# M18_lcq_20140714.net
KiCad netlist of a schematic drawn in Altium Designer
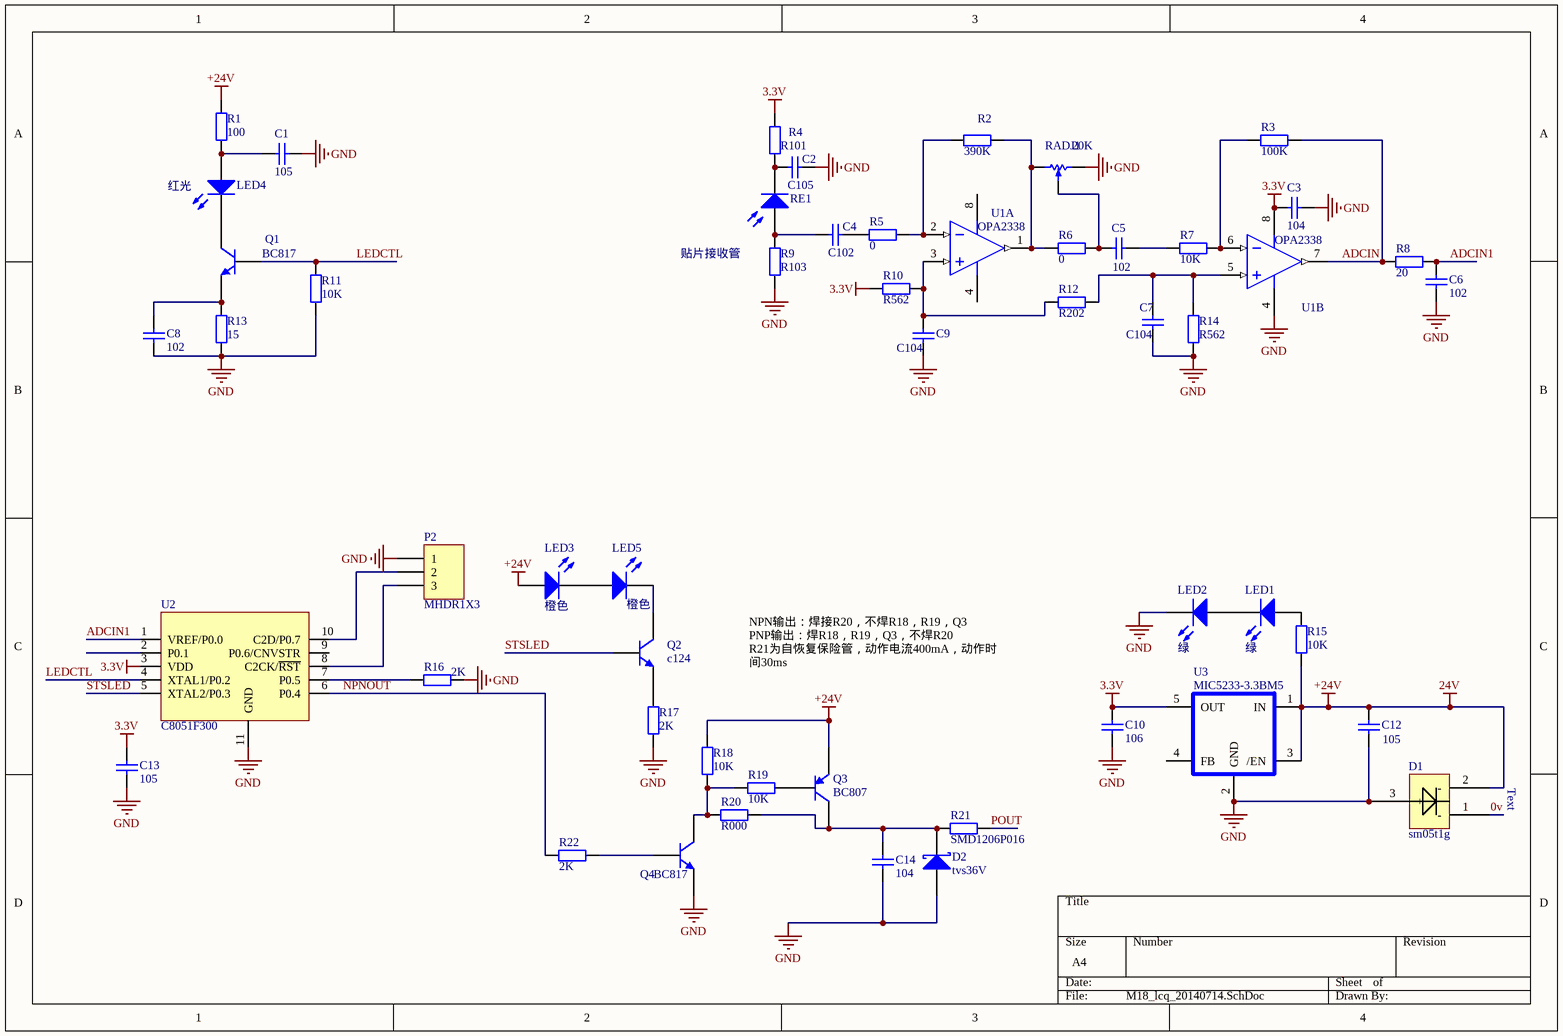
[diagram p0: M18_lcq_20140714.SchDoc]

(export (version "E")
  (design (tool "Eeschema 10.0.6"))
  (components
    (comp (ref "C1")
      (value "105")
      (footprint "C0805")
      (description "Capacitor")
      (fields (field (name "PUBLISHER") "Altium Limited"))
      (libsource (lib "TMJD1.0") (part "Cap"))
    )
    (comp (ref "C2")
      (value "C105")
      (footprint "C0603")
      (description "Capacitor")
      (fields (field (name "Comment") "C104") (field (name "PUBLISHER") "Altium Limited"))
      (libsource (lib "TMJD1.0") (part "Cap"))
    )
    (comp (ref "C3")
      (value "104")
      (footprint "C0805")
      (description "Capacitor")
      (fields (field (name "Comment") "C106") (field (name "PUBLISHER") "Altium Limited"))
      (libsource (lib "TMJD1.0") (part "Cap"))
    )
    (comp (ref "C4")
      (value "C102")
      (footprint "C0603")
      (description "Capacitor")
      (fields (field (name "Comment") "C104") (field (name "PUBLISHER") "Altium Limited"))
      (libsource (lib "TMJD1.0") (part "Cap"))
    )
    (comp (ref "C5")
      (value "102")
      (footprint "C0603")
      (description "Capacitor")
      (fields (field (name "Comment") "C104") (field (name "PUBLISHER") "Altium Limited"))
      (libsource (lib "TMJD1.0") (part "Cap"))
    )
    (comp (ref "C6")
      (value "102")
      (footprint "C0603")
      (description "Capacitor")
      (fields (field (name "Comment") "C104") (field (name "PUBLISHER") "Altium Limited"))
      (libsource (lib "TMJD1.0") (part "Cap"))
    )
    (comp (ref "C7")
      (value "C104")
      (footprint "C0603")
      (description "Capacitor")
      (fields (field (name "PUBLISHER") "Altium Limited"))
      (libsource (lib "TMJD1.0") (part "Cap"))
    )
    (comp (ref "C8")
      (value "102")
      (footprint "C0603")
      (description "Capacitor")
      (fields (field (name "Comment") "C104") (field (name "PUBLISHER") "Altium Limited"))
      (libsource (lib "TMJD1.0") (part "Cap"))
    )
    (comp (ref "C9")
      (value "C104")
      (footprint "C0603")
      (description "Capacitor")
      (fields (field (name "PUBLISHER") "Altium Limited"))
      (libsource (lib "TMJD1.0") (part "Cap"))
    )
    (comp (ref "C10")
      (value "106")
      (footprint "C0805")
      (description "Capacitor")
      (fields (field (name "Comment") "C106") (field (name "PUBLISHER") "Altium Limited"))
      (libsource (lib "TMJD1.0") (part "Cap"))
    )
    (comp (ref "C12")
      (value "105")
      (footprint "C0805")
      (description "Capacitor")
      (fields (field (name "PUBLISHER") "Altium Limited"))
      (libsource (lib "TMJD1.0") (part "Cap"))
    )
    (comp (ref "C13")
      (value "105")
      (footprint "C0805")
      (description "Capacitor")
      (fields (field (name "Comment") "C106") (field (name "PUBLISHER") "Altium Limited"))
      (libsource (lib "TMJD1.0") (part "Cap"))
    )
    (comp (ref "C14")
      (value "104")
      (footprint "C0603")
      (description "Capacitor")
      (fields (field (name "Comment") "C104") (field (name "PUBLISHER") "Altium Limited"))
      (libsource (lib "TMJD1.0") (part "Cap"))
    )
    (comp (ref "D1") (value "sm05t1g") (footprint "SOT23A") (libsource (lib "sm05t1g") (part "sm05t1g")))
    (comp (ref "D2")
      (value "tvs36V")
      (footprint "QQ2440V3封装库:3216A")
      (description "Schottky Diode")
      (fields (field (name "PUBLISHER") "Altium Limited"))
      (libsource (lib "*") (part "D Schottky"))
    )
    (comp (ref "LED1")
      (value "绿")
      (footprint "d0603")
      (description "Typical INFRARED GaAs LED")
      (fields (field (name "PUBLISHER") "Altium Limited"))
      (libsource (lib "Miscellaneous Devices") (part "LED0"))
    )
    (comp (ref "LED2")
      (value "绿")
      (footprint "d0603")
      (description "Typical INFRARED GaAs LED")
      (fields (field (name "PUBLISHER") "Altium Limited"))
      (libsource (lib "Miscellaneous Devices") (part "LED0"))
    )
    (comp (ref "LED3")
      (value "橙色")
      (footprint "d0603")
      (description "Typical INFRARED GaAs LED")
      (fields (field (name "PUBLISHER") "Altium Limited"))
      (libsource (lib "Miscellaneous Devices") (part "LED0"))
    )
    (comp (ref "LED4")
      (value "红光")
      (footprint "LED-1210")
      (description "Typical INFRARED GaAs LED")
      (fields (field (name "PUBLISHER") "Altium Limited"))
      (libsource (lib "Miscellaneous Devices") (part "LED0"))
    )
    (comp (ref "LED5")
      (value "橙色")
      (footprint "d0603")
      (description "Typical INFRARED GaAs LED")
      (fields (field (name "PUBLISHER") "Altium Limited"))
      (libsource (lib "Miscellaneous Devices") (part "LED0"))
    )
    (comp (ref "P2")
      (value "MHDR1X3")
      (footprint "MHDR1X3")
      (description "Header, 3-Pin")
      (fields (field (name "PUBLISHER") "Altium Limited"))
      (libsource (lib "Miscellaneous Connectors") (part "MHDR1X3"))
    )
    (comp (ref "Q1")
      (value "BC817")
      (footprint "SOT23A")
      (description "NPN Switching Transistor")
      (fields (field (name "PUBLISHER") "Altium Limited"))
      (libsource (lib "*") (part "MMBT3904"))
    )
    (comp (ref "Q2")
      (value "c124")
      (footprint "SOT23A")
      (description "NPN Switching Transistor")
      (fields (field (name "PUBLISHER") "Altium Limited"))
      (libsource (lib "*") (part "MMBT3904"))
    )
    (comp (ref "Q3")
      (value "BC807")
      (footprint "SOT23A")
      (description "PNP Switching Transistor")
      (fields (field (name "PUBLISHER") "Altium Limited"))
      (libsource (lib "Philips Discrete BJT - Low Power") (part "MMBT3906"))
    )
    (comp (ref "Q4")
      (value "BC817")
      (footprint "SOT23A")
      (description "NPN Switching Transistor")
      (fields (field (name "PUBLISHER") "Altium Limited"))
      (libsource (lib "*") (part "MMBT3904"))
    )
    (comp (ref "R1")
      (value "100")
      (footprint "R0603")
      (description "Resistor")
      (fields (field (name "PUBLISHER") "Altium Limited"))
      (libsource (lib "") (part "Res2_3"))
    )
    (comp (ref "R2")
      (value "390K")
      (footprint "R0603-A")
      (description "Resistor")
      (fields (field (name "PUBLISHER") "Altium Limited"))
      (libsource (lib "") (part "Res2_2"))
    )
    (comp (ref "R3")
      (value "100K")
      (footprint "R0603-A")
      (description "Resistor")
      (fields (field (name "PUBLISHER") "Altium Limited"))
      (libsource (lib "") (part "Res2_2"))
    )
    (comp (ref "R4")
      (value "R101")
      (footprint "R0603-A")
      (description "Resistor")
      (fields (field (name "PUBLISHER") "Altium Limited"))
      (libsource (lib "") (part "Res2_3"))
    )
    (comp (ref "R5")
      (value "0")
      (footprint "R0603-A")
      (description "Resistor")
      (fields (field (name "PUBLISHER") "Altium Limited"))
      (libsource (lib "") (part "Res2_2"))
    )
    (comp (ref "R6")
      (value "0")
      (footprint "R0603-A")
      (description "Resistor")
      (fields (field (name "PUBLISHER") "Altium Limited"))
      (libsource (lib "") (part "Res2_2"))
    )
    (comp (ref "R7")
      (value "10K")
      (footprint "R0603-A")
      (description "Resistor")
      (fields (field (name "PUBLISHER") "Altium Limited"))
      (libsource (lib "") (part "Res2_1"))
    )
    (comp (ref "R8")
      (value "20")
      (footprint "R0603-A")
      (description "Resistor")
      (fields (field (name "PUBLISHER") "Altium Limited"))
      (libsource (lib "") (part "Res2_2"))
    )
    (comp (ref "R9")
      (value "R103")
      (footprint "R0603-A")
      (description "Resistor")
      (fields (field (name "PUBLISHER") "Altium Limited"))
      (libsource (lib "") (part "Res2_3"))
    )
    (comp (ref "R10")
      (value "R562")
      (footprint "R0603-A")
      (description "Resistor")
      (fields (field (name "PUBLISHER") "Altium Limited"))
      (libsource (lib "") (part "Res2_1"))
    )
    (comp (ref "R11")
      (value "10K")
      (footprint "R0603-A")
      (description "Resistor")
      (fields (field (name "PUBLISHER") "Altium Limited"))
      (libsource (lib "Miscellaneous Devices") (part "Res2"))
    )
    (comp (ref "R12")
      (value "R202")
      (footprint "R0603-A")
      (description "Resistor")
      (fields (field (name "PUBLISHER") "Altium Limited"))
      (libsource (lib "") (part "Res2_2"))
    )
    (comp (ref "R13")
      (value "15")
      (footprint "R0603-A")
      (description "Resistor")
      (fields (field (name "PUBLISHER") "Altium Limited"))
      (libsource (lib "Miscellaneous Devices") (part "Res2"))
    )
    (comp (ref "R14")
      (value "R562")
      (footprint "R0603-A")
      (description "Resistor")
      (fields (field (name "PUBLISHER") "Altium Limited"))
      (libsource (lib "") (part "Res2_3"))
    )
    (comp (ref "R15")
      (value "10K")
      (footprint "R0603-A")
      (description "Resistor")
      (fields (field (name "PUBLISHER") "Altium Limited"))
      (libsource (lib "Miscellaneous Devices") (part "Res2"))
    )
    (comp (ref "R16")
      (value "2K")
      (footprint "R0603-A")
      (description "Resistor")
      (fields (field (name "PUBLISHER") "Altium Limited"))
      (libsource (lib "") (part "Res2_2"))
    )
    (comp (ref "R17")
      (value "2K")
      (footprint "R0603-A")
      (description "Resistor")
      (fields (field (name "PUBLISHER") "Altium Limited"))
      (libsource (lib "Miscellaneous Devices") (part "Res2"))
    )
    (comp (ref "R18")
      (value "10K")
      (footprint "R0603-A")
      (description "Resistor")
      (fields (field (name "PUBLISHER") "Altium Limited"))
      (libsource (lib "") (part "Res2_3"))
    )
    (comp (ref "R19")
      (value "10K")
      (footprint "R0603-A")
      (description "Resistor")
      (fields (field (name "PUBLISHER") "Altium Limited"))
      (libsource (lib "") (part "Res2_2"))
    )
    (comp (ref "R20")
      (value "R000")
      (footprint "R0603-A")
      (description "Resistor")
      (fields (field (name "PUBLISHER") "Altium Limited"))
      (libsource (lib "") (part "Res2_2"))
    )
    (comp (ref "R21")
      (value "SMD1206P016")
      (footprint "QQ2440V3封装库:3216A")
      (description "Resistor")
      (fields (field (name "PUBLISHER") "Altium Limited"))
      (libsource (lib "") (part "Res2_2"))
    )
    (comp (ref "R22")
      (value "2K")
      (footprint "R0603-A")
      (description "Resistor")
      (fields (field (name "PUBLISHER") "Altium Limited"))
      (libsource (lib "") (part "Res2_1"))
    )
    (comp (ref "RADJ1")
      (value "20K")
      (footprint "POT4MM-2")
      (description "Square Trimming Potentiometer")
      (fields (field (name "PUBLISHER") "Altium Limited"))
      (libsource (lib "Miscellaneous Devices") (part "RPot SM"))
    )
    (comp (ref "RE1")
      (value "贴片接收管")
      (footprint "LED-1210")
      (description "Photosensitive Diode")
      (fields (field (name "PUBLISHER") "Altium Limited"))
      (libsource (lib "Miscellaneous Devices") (part "Photo Sen"))
    )
    (comp (ref "U1")
      (value "OPA2338")
      (footprint "SOT23-8")
      (description "Dual Low Noise, Audio Amplifier")
      (fields (field (name "PUBLISHER") "Altium Limited"))
      (libsource (lib "Motorola Amplifier Audio Amplifier") (part "LM833D"))
    )
    (comp (ref "U2")
      (value "C8051F300")
      (footprint "C8051F330:IC*")
      (libsource (lib "集成块") (part "PIC16C505"))
    )
    (comp (ref "U3")
      (value "MIC5233-3.3BM5")
      (footprint "SOT-457")
      (libsource (lib "电源管理") (part "TPS77001"))
    )
  )
  (nets
    (net (code "1") (name "+24V") (class "Default")
      (node (ref "C12") (pin "1") (pinfunction "1_1") (pintype "passive"))
      (node (ref "D1") (pin "2") (pinfunction "-_2") (pintype "passive"))
      (node (ref "LED3") (pin "1") (pinfunction "A_1") (pintype "passive"))
      (node (ref "Q3") (pin "2") (pinfunction "E_2") (pintype "passive"))
      (node (ref "R1") (pin "1") (pinfunction "1_1") (pintype "passive"))
      (node (ref "R15") (pin "1") (pinfunction "1_1") (pintype "passive"))
      (node (ref "R18") (pin "1") (pinfunction "1_1") (pintype "passive"))
      (node (ref "U3") (pin "1") (pinfunction "IN_1") (pintype "passive"))
      (node (ref "U3") (pin "3") (pinfunction "/EN_3") (pintype "passive"))
    )
    (net (code "2") (name "/0v") (class "Default")
      (node (ref "D1") (pin "1") (pinfunction "-_1") (pintype "passive"))
    )
    (net (code "3") (name "/ADCIN") (class "Default")
      (node (ref "R3") (pin "2") (pinfunction "2_2") (pintype "passive"))
      (node (ref "R8") (pin "1") (pinfunction "1_1") (pintype "passive"))
      (node (ref "U1") (pin "7") (pinfunction "OUT_7") (pintype "output"))
    )
    (net (code "4") (name "/ADCIN1") (class "Default")
      (node (ref "C6") (pin "2") (pinfunction "2_2") (pintype "passive"))
      (node (ref "R8") (pin "2") (pinfunction "2_2") (pintype "passive"))
      (node (ref "U2") (pin "1") (pinfunction "VREF/P0.0_1") (pintype "passive"))
    )
    (net (code "5") (name "/LEDCTL") (class "Default")
      (node (ref "Q1") (pin "1") (pinfunction "B_1") (pintype "passive"))
      (node (ref "R11") (pin "2") (pinfunction "2_2") (pintype "passive"))
      (node (ref "U2") (pin "4") (pinfunction "XTAL1/P0.2_4") (pintype "passive"))
    )
    (net (code "6") (name "/NPNOUT") (class "Default")
      (node (ref "R22") (pin "2") (pinfunction "2_2") (pintype "passive"))
      (node (ref "U2") (pin "6") (pinfunction "P0.4_6") (pintype "passive"))
    )
    (net (code "7") (name "/POUT") (class "Default")
      (node (ref "R21") (pin "2") (pinfunction "2_2") (pintype "passive"))
    )
    (net (code "8") (name "/STSLED") (class "Default")
      (node (ref "Q2") (pin "1") (pinfunction "B_1") (pintype "passive"))
      (node (ref "U2") (pin "5") (pinfunction "XTAL2/P0.3_5") (pintype "passive"))
    )
    (net (code "9") (name "3.3V") (class "Default")
      (node (ref "C10") (pin "1") (pinfunction "1_1") (pintype "passive"))
      (node (ref "C13") (pin "1") (pinfunction "1_1") (pintype "passive"))
      (node (ref "C3") (pin "1") (pinfunction "1_1") (pintype "passive"))
      (node (ref "R10") (pin "2") (pinfunction "2_2") (pintype "passive"))
      (node (ref "R4") (pin "1") (pinfunction "1_1") (pintype "passive"))
      (node (ref "U1") (pin "8") (pinfunction "VCC_8") (pintype "power_in"))
      (node (ref "U2") (pin "3") (pinfunction "VDD_3") (pintype "passive"))
      (node (ref "U3") (pin "5") (pinfunction "OUT_5") (pintype "passive"))
    )
    (net (code "10") (name "GND") (class "Default")
      (node (ref "C1") (pin "2") (pinfunction "2_2") (pintype "passive"))
      (node (ref "C10") (pin "2") (pinfunction "2_2") (pintype "passive"))
      (node (ref "C12") (pin "2") (pinfunction "2_2") (pintype "passive"))
      (node (ref "C13") (pin "2") (pinfunction "2_2") (pintype "passive"))
      (node (ref "C14") (pin "2") (pinfunction "2_2") (pintype "passive"))
      (node (ref "C2") (pin "2") (pinfunction "2_2") (pintype "passive"))
      (node (ref "C3") (pin "2") (pinfunction "2_2") (pintype "passive"))
      (node (ref "C6") (pin "1") (pinfunction "1_1") (pintype "passive"))
      (node (ref "C7") (pin "2") (pinfunction "2_2") (pintype "passive"))
      (node (ref "C8") (pin "2") (pinfunction "2_2") (pintype "passive"))
      (node (ref "C9") (pin "2") (pinfunction "2_2") (pintype "passive"))
      (node (ref "D1") (pin "3") (pinfunction "+_3") (pintype "passive"))
      (node (ref "D2") (pin "1") (pinfunction "A_1") (pintype "passive"))
      (node (ref "LED2") (pin "2") (pinfunction "K_2") (pintype "passive"))
      (node (ref "P2") (pin "1") (pinfunction "1_1") (pintype "passive"))
      (node (ref "Q4") (pin "2") (pinfunction "E_2") (pintype "passive"))
      (node (ref "R11") (pin "1") (pinfunction "1_1") (pintype "passive"))
      (node (ref "R13") (pin "1") (pinfunction "1_1") (pintype "passive"))
      (node (ref "R14") (pin "2") (pinfunction "2_2") (pintype "passive"))
      (node (ref "R16") (pin "2") (pinfunction "2_2") (pintype "passive"))
      (node (ref "R17") (pin "1") (pinfunction "1_1") (pintype "passive"))
      (node (ref "R9") (pin "2") (pinfunction "2_2") (pintype "passive"))
      (node (ref "RADJ1") (pin "CW") (pinfunction "+_CW") (pintype "passive"))
      (node (ref "U1") (pin "4") (pinfunction "VEE_4") (pintype "power_in"))
      (node (ref "U2") (pin "11") (pinfunction "GND_11") (pintype "passive"))
      (node (ref "U3") (pin "2") (pinfunction "GND_2") (pintype "passive"))
    )
    (net (code "11") (name "Net-(C4-Pad2)") (class "Default")
      (node (ref "C4") (pin "2") (pinfunction "2_2") (pintype "passive"))
      (node (ref "R5") (pin "1") (pinfunction "1_1") (pintype "passive"))
    )
    (net (code "12") (name "Net-(C5-Pad1)") (class "Default")
      (node (ref "C5") (pin "1") (pinfunction "1_1") (pintype "passive"))
      (node (ref "R6") (pin "2") (pinfunction "2_2") (pintype "passive"))
      (node (ref "RADJ1") (pin "W") (pinfunction "W_W") (pintype "passive"))
    )
    (net (code "13") (name "Net-(C5-Pad2)") (class "Default")
      (node (ref "C5") (pin "2") (pinfunction "2_2") (pintype "passive"))
      (node (ref "R7") (pin "2") (pinfunction "2_2") (pintype "passive"))
    )
    (net (code "14") (name "Net-(D2-K)") (class "Default")
      (node (ref "C14") (pin "1") (pinfunction "1_1") (pintype "passive"))
      (node (ref "D2") (pin "2") (pinfunction "K_2") (pintype "passive"))
      (node (ref "Q3") (pin "3") (pinfunction "C_3") (pintype "passive"))
      (node (ref "R20") (pin "2") (pinfunction "2_2") (pintype "passive"))
      (node (ref "R21") (pin "1") (pinfunction "1_1") (pintype "passive"))
    )
    (net (code "15") (name "Net-(LED1-A)") (class "Default")
      (node (ref "LED1") (pin "1") (pinfunction "A_1") (pintype "passive"))
      (node (ref "R15") (pin "2") (pinfunction "2_2") (pintype "passive"))
    )
    (net (code "16") (name "Net-(LED1-K)") (class "Default")
      (node (ref "LED1") (pin "2") (pinfunction "K_2") (pintype "passive"))
      (node (ref "LED2") (pin "1") (pinfunction "A_1") (pintype "passive"))
    )
    (net (code "17") (name "Net-(LED3-K)") (class "Default")
      (node (ref "LED3") (pin "2") (pinfunction "K_2") (pintype "passive"))
      (node (ref "LED5") (pin "1") (pinfunction "A_1") (pintype "passive"))
    )
    (net (code "18") (name "Net-(LED4-A)") (class "Default")
      (node (ref "C1") (pin "1") (pinfunction "1_1") (pintype "passive"))
      (node (ref "LED4") (pin "1") (pinfunction "A_1") (pintype "passive"))
      (node (ref "R1") (pin "2") (pinfunction "2_2") (pintype "passive"))
    )
    (net (code "19") (name "Net-(LED4-K)") (class "Default")
      (node (ref "LED4") (pin "2") (pinfunction "K_2") (pintype "passive"))
      (node (ref "Q1") (pin "3") (pinfunction "C_3") (pintype "passive"))
    )
    (net (code "20") (name "Net-(LED5-K)") (class "Default")
      (node (ref "LED5") (pin "2") (pinfunction "K_2") (pintype "passive"))
      (node (ref "Q2") (pin "3") (pinfunction "C_3") (pintype "passive"))
    )
    (net (code "21") (name "Net-(Q1-E)") (class "Default")
      (node (ref "C8") (pin "1") (pinfunction "1_1") (pintype "passive"))
      (node (ref "Q1") (pin "2") (pinfunction "E_2") (pintype "passive"))
      (node (ref "R13") (pin "2") (pinfunction "2_2") (pintype "passive"))
    )
    (net (code "22") (name "Net-(Q2-E)") (class "Default")
      (node (ref "Q2") (pin "2") (pinfunction "E_2") (pintype "passive"))
      (node (ref "R17") (pin "2") (pinfunction "2_2") (pintype "passive"))
    )
    (net (code "23") (name "Net-(Q3-B)") (class "Default")
      (node (ref "Q3") (pin "1") (pinfunction "B_1") (pintype "passive"))
      (node (ref "R19") (pin "2") (pinfunction "2_2") (pintype "passive"))
    )
    (net (code "24") (name "Net-(Q4-B)") (class "Default")
      (node (ref "Q4") (pin "1") (pinfunction "B_1") (pintype "passive"))
      (node (ref "R22") (pin "1") (pinfunction "1_1") (pintype "passive"))
    )
    (net (code "25") (name "Net-(Q4-C)") (class "Default")
      (node (ref "Q4") (pin "3") (pinfunction "C_3") (pintype "passive"))
      (node (ref "R18") (pin "2") (pinfunction "2_2") (pintype "passive"))
      (node (ref "R19") (pin "1") (pinfunction "1_1") (pintype "passive"))
      (node (ref "R20") (pin "1") (pinfunction "1_1") (pintype "passive"))
    )
    (net (code "26") (name "Net-(RADJ1--)") (class "Default")
      (node (ref "R2") (pin "2") (pinfunction "2_2") (pintype "passive"))
      (node (ref "R6") (pin "1") (pinfunction "1_1") (pintype "passive"))
      (node (ref "RADJ1") (pin "CCW") (pinfunction "-_CCW") (pintype "passive"))
      (node (ref "U1") (pin "1") (pinfunction "OUT_1") (pintype "output"))
    )
    (net (code "27") (name "Net-(RE1-A)") (class "Default")
      (node (ref "C4") (pin "1") (pinfunction "1_1") (pintype "passive"))
      (node (ref "R9") (pin "1") (pinfunction "1_1") (pintype "passive"))
      (node (ref "RE1") (pin "1") (pinfunction "A_1") (pintype "passive"))
    )
    (net (code "28") (name "Net-(RE1-K)") (class "Default")
      (node (ref "C2") (pin "1") (pinfunction "1_1") (pintype "passive"))
      (node (ref "R4") (pin "2") (pinfunction "2_2") (pintype "passive"))
      (node (ref "RE1") (pin "2") (pinfunction "K_2") (pintype "passive"))
    )
    (net (code "29") (name "Net-(U1A-IN+)") (class "Default")
      (node (ref "C9") (pin "1") (pinfunction "1_1") (pintype "passive"))
      (node (ref "R10") (pin "1") (pinfunction "1_1") (pintype "passive"))
      (node (ref "R12") (pin "1") (pinfunction "1_1") (pintype "passive"))
      (node (ref "U1") (pin "3") (pinfunction "IN+_3") (pintype "input"))
    )
    (net (code "30") (name "Net-(U1A-IN-)") (class "Default")
      (node (ref "R2") (pin "1") (pinfunction "1_1") (pintype "passive"))
      (node (ref "R5") (pin "2") (pinfunction "2_2") (pintype "passive"))
      (node (ref "U1") (pin "2") (pinfunction "IN-_2") (pintype "input"))
    )
    (net (code "31") (name "Net-(U1B-IN+)") (class "Default")
      (node (ref "C7") (pin "1") (pinfunction "1_1") (pintype "passive"))
      (node (ref "R12") (pin "2") (pinfunction "2_2") (pintype "passive"))
      (node (ref "R14") (pin "1") (pinfunction "1_1") (pintype "passive"))
      (node (ref "U1") (pin "5") (pinfunction "IN+_5") (pintype "input"))
    )
    (net (code "32") (name "Net-(U1B-IN-)") (class "Default")
      (node (ref "R3") (pin "1") (pinfunction "1_1") (pintype "passive"))
      (node (ref "R7") (pin "1") (pinfunction "1_1") (pintype "passive"))
      (node (ref "U1") (pin "6") (pinfunction "IN-_6") (pintype "input"))
    )
    (net (code "33") (name "Net-(U2-C2CK{slash}~{RST})") (class "Default")
      (node (ref "P2") (pin "3") (pinfunction "3_3") (pintype "passive"))
      (node (ref "U2") (pin "8") (pinfunction "C2CK/~{RST}_8") (pintype "passive"))
    )
    (net (code "34") (name "Net-(U2-C2D{slash}P0.7)") (class "Default")
      (node (ref "P2") (pin "2") (pinfunction "2_2") (pintype "passive"))
      (node (ref "U2") (pin "10") (pinfunction "C2D/P0.7_10") (pintype "passive"))
    )
    (net (code "35") (name "Net-(U2-P0.5)") (class "Default")
      (node (ref "R16") (pin "1") (pinfunction "1_1") (pintype "passive"))
      (node (ref "U2") (pin "7") (pinfunction "P0.5_7") (pintype "passive"))
    )
    (net (code "36") (name "unconnected-(U1A-VCC-Pad8)") (class "Default")
      (node (ref "U1") (pin "8") (pinfunction "VCC_8") (pintype "power_in"))
    )
    (net (code "37") (name "unconnected-(U1A-VEE-Pad4)") (class "Default")
      (node (ref "U1") (pin "4") (pinfunction "VEE_4") (pintype "power_in"))
    )
    (net (code "38") (name "unconnected-(U2-P0.1-Pad2)") (class "Default")
      (node (ref "U2") (pin "2") (pinfunction "P0.1_2") (pintype "passive"))
    )
    (net (code "39") (name "unconnected-(U2-P0.6{slash}CNVSTR-Pad9)") (class "Default")
      (node (ref "U2") (pin "9") (pinfunction "P0.6/CNVSTR_9") (pintype "passive"))
    )
    (net (code "40") (name "unconnected-(U3-FB-Pad4)") (class "Default")
      (node (ref "U3") (pin "4") (pinfunction "FB_4") (pintype "passive"))
    )
  )
)
